# Set-Mile-Bottom.net
KiCad netlist of a schematic drawn in EAGLE
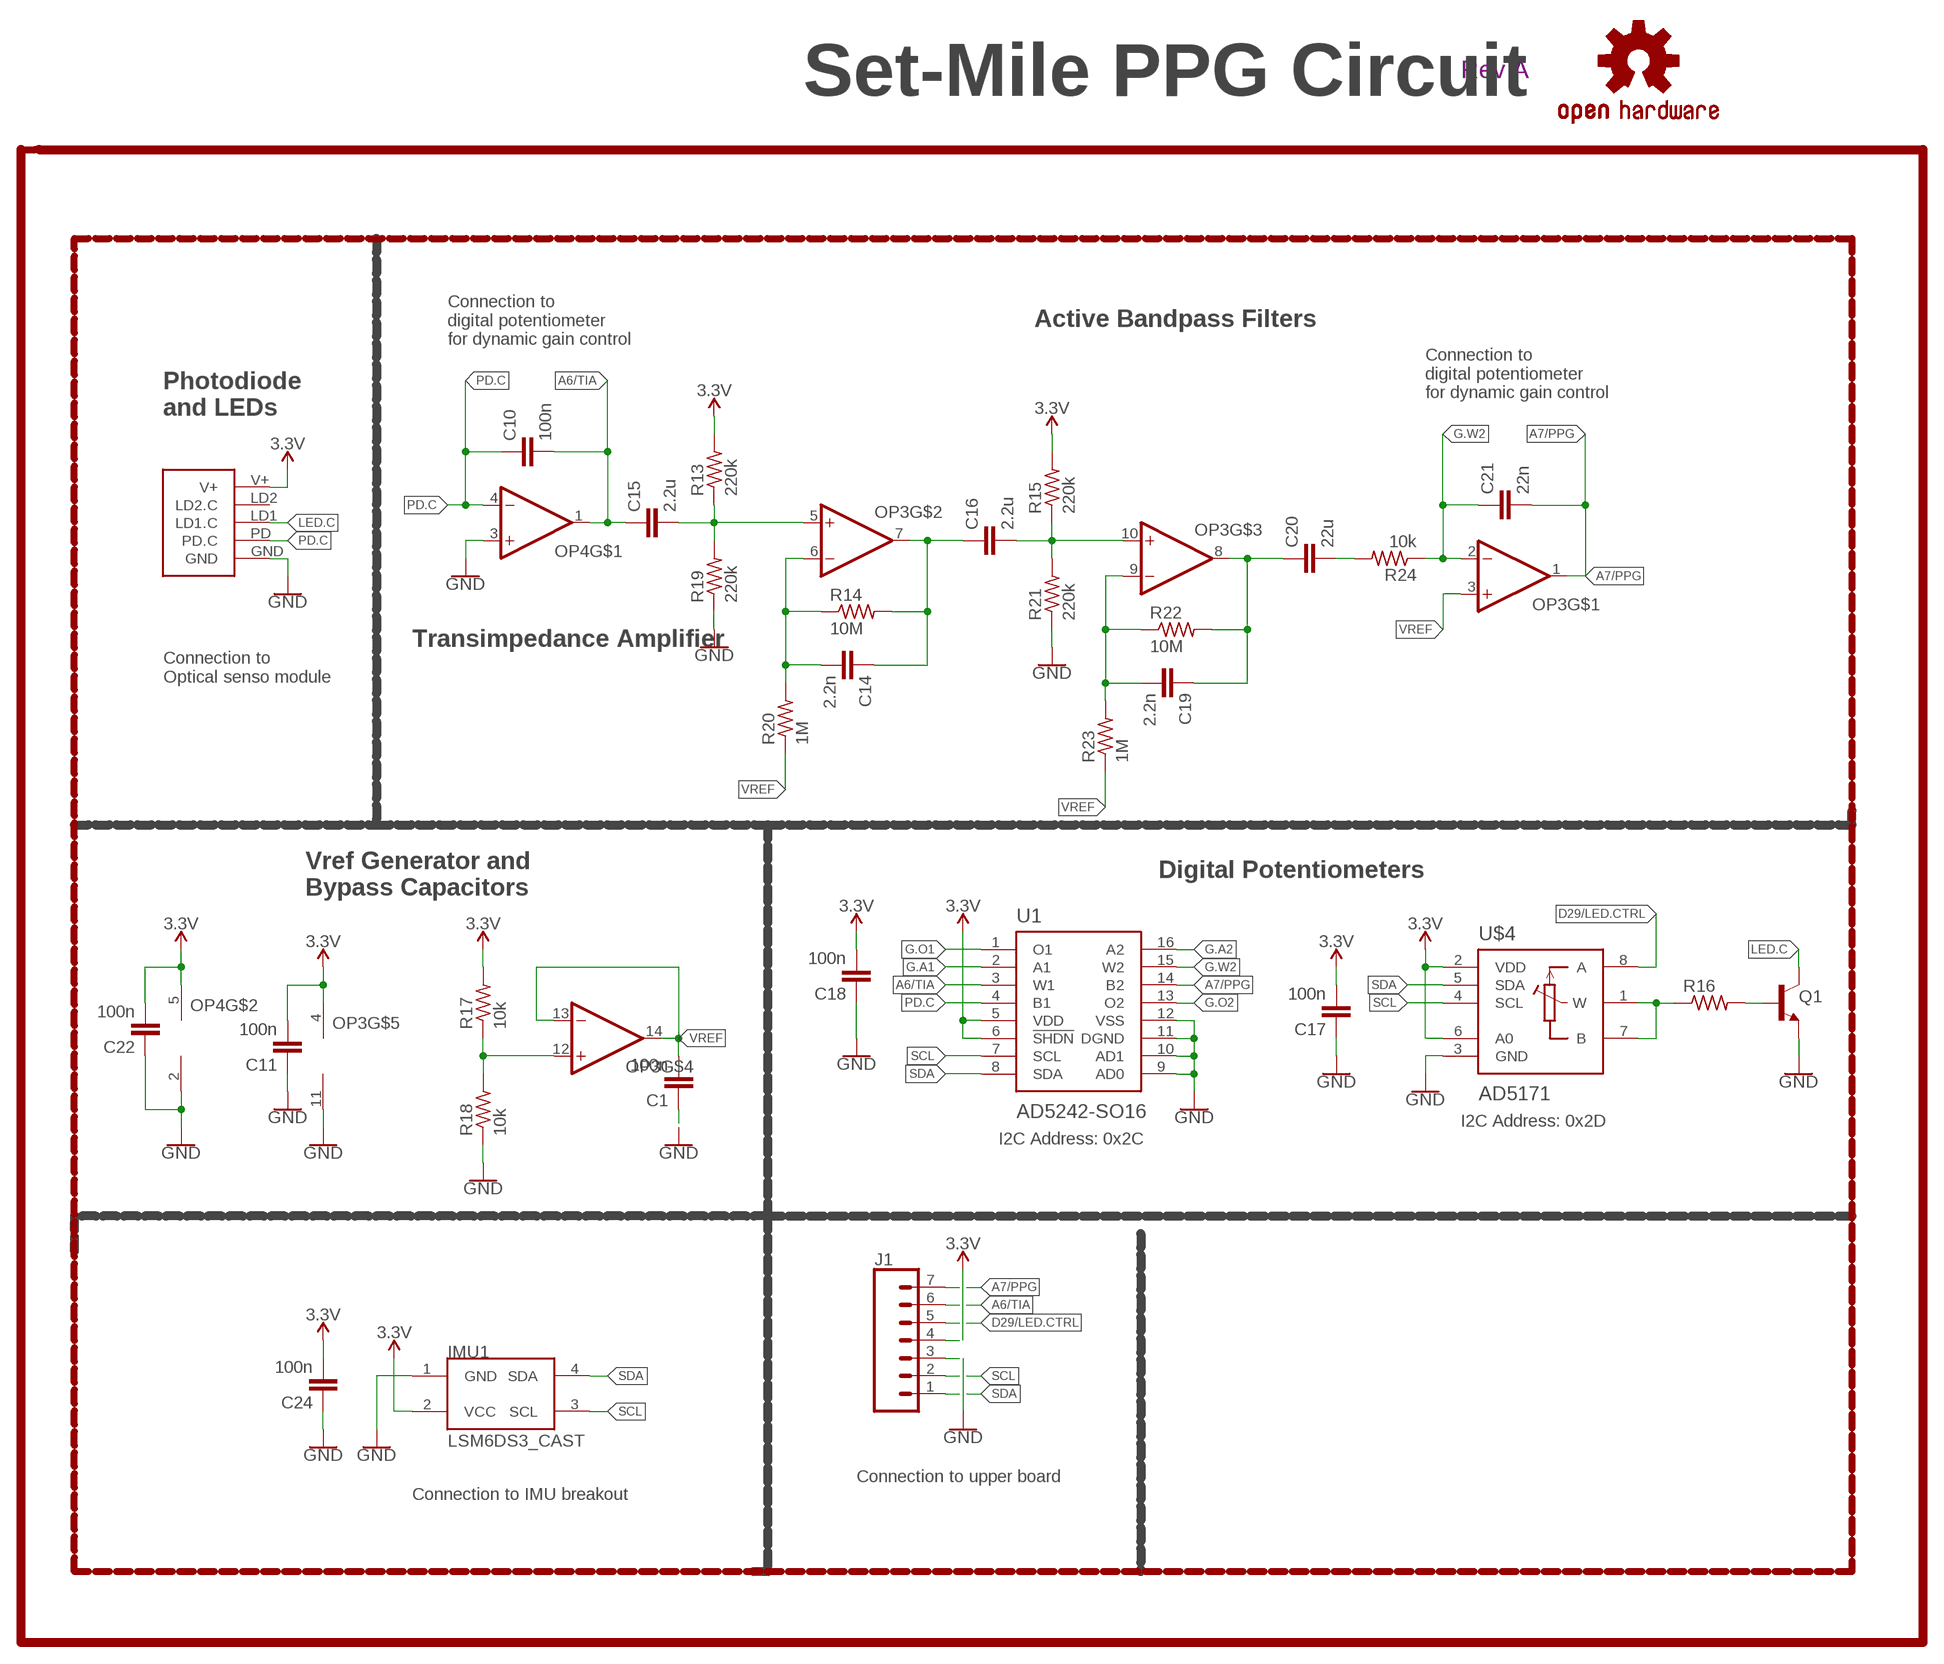
[diagram p0: schematic, sheet 1]

(export (version "E")
  (design (tool "Eeschema 10.0.6"))
  (components
    (comp (ref "C1")
      (value "100n")
      (footprint "eagle-import:C0603")
      (libsource (lib "eagle-import") (part "CAPACITOR0603"))
    )
    (comp (ref "C10")
      (value "100n")
      (footprint "eagle-import:C0603")
      (libsource (lib "eagle-import") (part "CAPACITOR0603"))
    )
    (comp (ref "C11")
      (value "100n")
      (footprint "eagle-import:C0603")
      (libsource (lib "eagle-import") (part "CAPACITOR0603"))
    )
    (comp (ref "C14")
      (value "2.2n")
      (footprint "eagle-import:C0603")
      (libsource (lib "eagle-import") (part "CAPACITOR0603"))
    )
    (comp (ref "C15")
      (value "2.2u")
      (footprint "eagle-import:C0603")
      (libsource (lib "eagle-import") (part "CAPACITOR0603"))
    )
    (comp (ref "C16")
      (value "2.2u")
      (footprint "eagle-import:C0603")
      (libsource (lib "eagle-import") (part "CAPACITOR0603"))
    )
    (comp (ref "C17")
      (value "100n")
      (footprint "eagle-import:C0603")
      (libsource (lib "eagle-import") (part "CAPACITOR0603"))
    )
    (comp (ref "C18")
      (value "100n")
      (footprint "eagle-import:C0603")
      (libsource (lib "eagle-import") (part "CAPACITOR0603"))
    )
    (comp (ref "C19")
      (value "2.2n")
      (footprint "eagle-import:C0603")
      (libsource (lib "eagle-import") (part "CAPACITOR0603"))
    )
    (comp (ref "C20")
      (value "22u")
      (footprint "eagle-import:C0603")
      (libsource (lib "eagle-import") (part "CAPACITOR0603"))
    )
    (comp (ref "C21")
      (value "22n")
      (footprint "eagle-import:C0603")
      (libsource (lib "eagle-import") (part "CAPACITOR0603"))
    )
    (comp (ref "C22")
      (value "100n")
      (footprint "eagle-import:C0603")
      (libsource (lib "eagle-import") (part "CAPACITOR0603"))
    )
    (comp (ref "C24")
      (value "100n")
      (footprint "eagle-import:C0603")
      (libsource (lib "eagle-import") (part "CAPACITOR0603"))
    )
    (comp (ref "IMU1")
      (value "LSM6DS3_CAST")
      (footprint "eagle-import:LSM6DS3_CAST")
      (libsource (lib "eagle-import") (part "LSM6DS3_CAST"))
    )
    (comp (ref "J1")
      (value "CONN_07-1.27MM")
      (footprint "eagle-import:1X07_1.27MM")
      (libsource (lib "eagle-import") (part "CONN_07-1.27MM"))
    )
    (comp (ref "LOGO1")
      (value "REVISION.A")
      (footprint "eagle-import:REV.A")
      (libsource (lib "eagle-import") (part "REVISION.A"))
    )
    (comp (ref "LOGO2")
      (value "OSHW-LOGOL")
      (footprint "eagle-import:OSHW-LOGO-L")
      (libsource (lib "eagle-import") (part "OSHW-LOGOL"))
    )
    (comp (ref "OP3")
      (value "OP-QUAD-SO14")
      (footprint "eagle-import:SO14")
      (libsource (lib "eagle-import") (part "OP-QUAD-SO14"))
    )
    (comp (ref "OP4")
      (value "OP-SINGLEOT")
      (footprint "eagle-import:SOT23-5")
      (libsource (lib "eagle-import") (part "OP-SINGLEOT"))
    )
    (comp (ref "Q1")
      (value "NPN-GENERIC")
      (footprint "eagle-import:SOT23-3")
      (libsource (lib "eagle-import") (part "NPN-GENERIC"))
    )
    (comp (ref "R13")
      (value "220k")
      (footprint "eagle-import:R0603")
      (libsource (lib "eagle-import") (part "RESISTOR0603"))
    )
    (comp (ref "R14")
      (value "10M")
      (footprint "eagle-import:R0603")
      (libsource (lib "eagle-import") (part "RESISTOR0603"))
    )
    (comp (ref "R15")
      (value "220k")
      (footprint "eagle-import:R0603")
      (libsource (lib "eagle-import") (part "RESISTOR0603"))
    )
    (comp (ref "R16")
      (value "RESISTOR0603")
      (footprint "eagle-import:R0603")
      (libsource (lib "eagle-import") (part "RESISTOR0603"))
    )
    (comp (ref "R17")
      (value "10k")
      (footprint "eagle-import:R0402")
      (libsource (lib "eagle-import") (part "RESISTOR0402"))
    )
    (comp (ref "R18")
      (value "10k")
      (footprint "eagle-import:R0402")
      (libsource (lib "eagle-import") (part "RESISTOR0402"))
    )
    (comp (ref "R19")
      (value "220k")
      (footprint "eagle-import:R0603")
      (libsource (lib "eagle-import") (part "RESISTOR0603"))
    )
    (comp (ref "R20")
      (value "1M")
      (footprint "eagle-import:R0603")
      (libsource (lib "eagle-import") (part "RESISTOR0603"))
    )
    (comp (ref "R21")
      (value "220k")
      (footprint "eagle-import:R0603")
      (libsource (lib "eagle-import") (part "RESISTOR0603"))
    )
    (comp (ref "R22")
      (value "10M")
      (footprint "eagle-import:R0603")
      (libsource (lib "eagle-import") (part "RESISTOR0603"))
    )
    (comp (ref "R23")
      (value "1M")
      (footprint "eagle-import:R0603")
      (libsource (lib "eagle-import") (part "RESISTOR0603"))
    )
    (comp (ref "R24")
      (value "10k")
      (footprint "eagle-import:R0603")
      (libsource (lib "eagle-import") (part "RESISTOR0603"))
    )
    (comp (ref "U$3")
      (value "PPG.MODULE.2")
      (footprint "eagle-import:PPG.MODULE.2")
      (libsource (lib "eagle-import") (part "PPG.MODULE.2"))
    )
    (comp (ref "U$4")
      (value "AD5171")
      (footprint "eagle-import:SOT-23-8")
      (libsource (lib "eagle-import") (part "AD5171"))
    )
    (comp (ref "U1")
      (value "AD5242-SO16")
      (footprint "eagle-import:SO16")
      (libsource (lib "eagle-import") (part "AD5242-SO16"))
    )
  )
  (nets
    (net (code "1") (name "3.3V") (class "Default")
      (node (ref "C11") (pin "2") (pinfunction "2_2") (pintype "passive"))
      (node (ref "C17") (pin "2") (pinfunction "2_2") (pintype "passive"))
      (node (ref "C18") (pin "2") (pinfunction "2_2") (pintype "passive"))
      (node (ref "C22") (pin "2") (pinfunction "2_2") (pintype "passive"))
      (node (ref "C24") (pin "2") (pinfunction "2_2") (pintype "passive"))
      (node (ref "IMU1") (pin "2") (pinfunction "VCC_2") (pintype "bidirectional"))
      (node (ref "J1") (pin "4") (pinfunction "4_4") (pintype "passive"))
      (node (ref "OP3") (pin "4") (pinfunction "V+_4") (pintype "power_in"))
      (node (ref "OP4") (pin "5") (pinfunction "V+_5") (pintype "power_in"))
      (node (ref "R13") (pin "2") (pinfunction "2_2") (pintype "passive"))
      (node (ref "R15") (pin "2") (pinfunction "2_2") (pintype "passive"))
      (node (ref "R17") (pin "2") (pinfunction "2_2") (pintype "passive"))
      (node (ref "U$3") (pin "V+") (pinfunction "V+_V+") (pintype "bidirectional"))
      (node (ref "U$4") (pin "2") (pinfunction "VDD_2") (pintype "bidirectional"))
      (node (ref "U$4") (pin "6") (pinfunction "A0_6") (pintype "bidirectional"))
      (node (ref "U1") (pin "5") (pinfunction "VDD_5") (pintype "bidirectional"))
      (node (ref "U1") (pin "6") (pinfunction "~{SHDN}_6") (pintype "bidirectional"))
    )
    (net (code "2") (name "A6{slash}TIA") (class "Default")
      (node (ref "C10") (pin "2") (pinfunction "2_2") (pintype "passive"))
      (node (ref "C15") (pin "1") (pinfunction "1_1") (pintype "passive"))
      (node (ref "J1") (pin "6") (pinfunction "6_6") (pintype "passive"))
      (node (ref "OP4") (pin "1") (pinfunction "OUT_1") (pintype "output"))
      (node (ref "U1") (pin "3") (pinfunction "W1_3") (pintype "bidirectional"))
    )
    (net (code "3") (name "A7{slash}PPG") (class "Default")
      (node (ref "C21") (pin "2") (pinfunction "2_2") (pintype "passive"))
      (node (ref "J1") (pin "7") (pinfunction "7_7") (pintype "passive"))
      (node (ref "OP3") (pin "1") (pinfunction "OUT_1") (pintype "output"))
      (node (ref "U1") (pin "14") (pinfunction "B2_14") (pintype "bidirectional"))
    )
    (net (code "4") (name "D29{slash}LED.CTRL") (class "Default")
      (node (ref "J1") (pin "5") (pinfunction "5_5") (pintype "passive"))
      (node (ref "U$4") (pin "8") (pinfunction "A_8") (pintype "bidirectional"))
    )
    (net (code "5") (name "G.A1") (class "Default")
      (node (ref "U1") (pin "2") (pinfunction "A1_2") (pintype "bidirectional"))
    )
    (net (code "6") (name "G.A2") (class "Default")
      (node (ref "U1") (pin "16") (pinfunction "A2_16") (pintype "bidirectional"))
    )
    (net (code "7") (name "G.O1") (class "Default")
      (node (ref "U1") (pin "1") (pinfunction "O1_1") (pintype "bidirectional"))
    )
    (net (code "8") (name "G.O2") (class "Default")
      (node (ref "U1") (pin "13") (pinfunction "O2_13") (pintype "bidirectional"))
    )
    (net (code "9") (name "G.W2") (class "Default")
      (node (ref "C21") (pin "1") (pinfunction "1_1") (pintype "passive"))
      (node (ref "OP3") (pin "2") (pinfunction "-IN_2") (pintype "input"))
      (node (ref "R24") (pin "1") (pinfunction "1_1") (pintype "passive"))
      (node (ref "U1") (pin "15") (pinfunction "W2_15") (pintype "bidirectional"))
    )
    (net (code "10") (name "GND") (class "Default")
      (node (ref "C1") (pin "1") (pinfunction "1_1") (pintype "passive"))
      (node (ref "C11") (pin "1") (pinfunction "1_1") (pintype "passive"))
      (node (ref "C17") (pin "1") (pinfunction "1_1") (pintype "passive"))
      (node (ref "C18") (pin "1") (pinfunction "1_1") (pintype "passive"))
      (node (ref "C22") (pin "1") (pinfunction "1_1") (pintype "passive"))
      (node (ref "C24") (pin "1") (pinfunction "1_1") (pintype "passive"))
      (node (ref "IMU1") (pin "1") (pinfunction "GND_1") (pintype "bidirectional"))
      (node (ref "J1") (pin "3") (pinfunction "3_3") (pintype "passive"))
      (node (ref "OP3") (pin "11") (pinfunction "V-_11") (pintype "power_in"))
      (node (ref "OP4") (pin "2") (pinfunction "V-_2") (pintype "power_in"))
      (node (ref "OP4") (pin "3") (pinfunction "+IN_3") (pintype "input"))
      (node (ref "Q1") (pin "2") (pinfunction "E_2") (pintype "passive"))
      (node (ref "R18") (pin "1") (pinfunction "1_1") (pintype "passive"))
      (node (ref "R19") (pin "1") (pinfunction "1_1") (pintype "passive"))
      (node (ref "R21") (pin "1") (pinfunction "1_1") (pintype "passive"))
      (node (ref "U$3") (pin "GND") (pinfunction "GND_GND") (pintype "bidirectional"))
      (node (ref "U$4") (pin "3") (pinfunction "GND_3") (pintype "bidirectional"))
      (node (ref "U1") (pin "10") (pinfunction "AD1_10") (pintype "bidirectional"))
      (node (ref "U1") (pin "11") (pinfunction "DGND_11") (pintype "bidirectional"))
      (node (ref "U1") (pin "12") (pinfunction "VSS_12") (pintype "bidirectional"))
      (node (ref "U1") (pin "9") (pinfunction "AD0_9") (pintype "bidirectional"))
    )
    (net (code "11") (name "LED.C") (class "Default")
      (node (ref "Q1") (pin "3") (pinfunction "C_3") (pintype "passive"))
      (node (ref "U$3") (pin "LD1") (pinfunction "LD1.C_LD1") (pintype "bidirectional"))
    )
    (net (code "12") (name "Net-(C20-Pad2)") (class "Default")
      (node (ref "C20") (pin "2") (pinfunction "2_2") (pintype "passive"))
      (node (ref "R24") (pin "2") (pinfunction "2_2") (pintype "passive"))
    )
    (net (code "13") (name "Net-(OP3B-+IN)") (class "Default")
      (node (ref "C15") (pin "2") (pinfunction "2_2") (pintype "passive"))
      (node (ref "OP3") (pin "5") (pinfunction "+IN_5") (pintype "input"))
      (node (ref "R13") (pin "1") (pinfunction "1_1") (pintype "passive"))
      (node (ref "R19") (pin "2") (pinfunction "2_2") (pintype "passive"))
    )
    (net (code "14") (name "Net-(OP3B--IN)") (class "Default")
      (node (ref "C14") (pin "2") (pinfunction "2_2") (pintype "passive"))
      (node (ref "OP3") (pin "6") (pinfunction "-IN_6") (pintype "input"))
      (node (ref "R14") (pin "1") (pinfunction "1_1") (pintype "passive"))
      (node (ref "R20") (pin "2") (pinfunction "2_2") (pintype "passive"))
    )
    (net (code "15") (name "Net-(OP3B-OUT)") (class "Default")
      (node (ref "C14") (pin "1") (pinfunction "1_1") (pintype "passive"))
      (node (ref "C16") (pin "1") (pinfunction "1_1") (pintype "passive"))
      (node (ref "OP3") (pin "7") (pinfunction "OUT_7") (pintype "output"))
      (node (ref "R14") (pin "2") (pinfunction "2_2") (pintype "passive"))
    )
    (net (code "16") (name "Net-(OP3C-+IN)") (class "Default")
      (node (ref "C16") (pin "2") (pinfunction "2_2") (pintype "passive"))
      (node (ref "OP3") (pin "10") (pinfunction "+IN_10") (pintype "input"))
      (node (ref "R15") (pin "1") (pinfunction "1_1") (pintype "passive"))
      (node (ref "R21") (pin "2") (pinfunction "2_2") (pintype "passive"))
    )
    (net (code "17") (name "Net-(OP3C--IN)") (class "Default")
      (node (ref "C19") (pin "2") (pinfunction "2_2") (pintype "passive"))
      (node (ref "OP3") (pin "9") (pinfunction "-IN_9") (pintype "input"))
      (node (ref "R22") (pin "1") (pinfunction "1_1") (pintype "passive"))
      (node (ref "R23") (pin "2") (pinfunction "2_2") (pintype "passive"))
    )
    (net (code "18") (name "Net-(OP3C-OUT)") (class "Default")
      (node (ref "C19") (pin "1") (pinfunction "1_1") (pintype "passive"))
      (node (ref "C20") (pin "1") (pinfunction "1_1") (pintype "passive"))
      (node (ref "OP3") (pin "8") (pinfunction "OUT_8") (pintype "output"))
      (node (ref "R22") (pin "2") (pinfunction "2_2") (pintype "passive"))
    )
    (net (code "19") (name "Net-(OP3D-+IN)") (class "Default")
      (node (ref "OP3") (pin "12") (pinfunction "+IN_12") (pintype "input"))
      (node (ref "R17") (pin "1") (pinfunction "1_1") (pintype "passive"))
      (node (ref "R18") (pin "2") (pinfunction "2_2") (pintype "passive"))
    )
    (net (code "20") (name "Net-(Q1-B)") (class "Default")
      (node (ref "Q1") (pin "1") (pinfunction "B_1") (pintype "passive"))
      (node (ref "R16") (pin "2") (pinfunction "2_2") (pintype "passive"))
    )
    (net (code "21") (name "Net-(U$4-B)") (class "Default")
      (node (ref "R16") (pin "1") (pinfunction "1_1") (pintype "passive"))
      (node (ref "U$4") (pin "1") (pinfunction "W_1") (pintype "bidirectional"))
      (node (ref "U$4") (pin "7") (pinfunction "B_7") (pintype "bidirectional"))
    )
    (net (code "22") (name "PD.C") (class "Default")
      (node (ref "C10") (pin "1") (pinfunction "1_1") (pintype "passive"))
      (node (ref "OP4") (pin "4") (pinfunction "-IN_4") (pintype "input"))
      (node (ref "U$3") (pin "PD") (pinfunction "PD.C_PD") (pintype "bidirectional"))
      (node (ref "U1") (pin "4") (pinfunction "B1_4") (pintype "bidirectional"))
    )
    (net (code "23") (name "SCL") (class "Default")
      (node (ref "IMU1") (pin "3") (pinfunction "SCL_3") (pintype "bidirectional"))
      (node (ref "J1") (pin "2") (pinfunction "2_2") (pintype "passive"))
      (node (ref "U$4") (pin "4") (pinfunction "SCL_4") (pintype "bidirectional"))
      (node (ref "U1") (pin "7") (pinfunction "SCL_7") (pintype "bidirectional"))
    )
    (net (code "24") (name "SDA") (class "Default")
      (node (ref "IMU1") (pin "4") (pinfunction "SDA_4") (pintype "bidirectional"))
      (node (ref "J1") (pin "1") (pinfunction "1_1") (pintype "passive"))
      (node (ref "U$4") (pin "5") (pinfunction "SDA_5") (pintype "bidirectional"))
      (node (ref "U1") (pin "8") (pinfunction "SDA_8") (pintype "bidirectional"))
    )
    (net (code "25") (name "VREF") (class "Default")
      (node (ref "C1") (pin "2") (pinfunction "2_2") (pintype "passive"))
      (node (ref "OP3") (pin "13") (pinfunction "-IN_13") (pintype "input"))
      (node (ref "OP3") (pin "14") (pinfunction "OUT_14") (pintype "output"))
      (node (ref "OP3") (pin "3") (pinfunction "+IN_3") (pintype "input"))
      (node (ref "R20") (pin "1") (pinfunction "1_1") (pintype "passive"))
      (node (ref "R23") (pin "1") (pinfunction "1_1") (pintype "passive"))
    )
    (net (code "26") (name "unconnected-(U$3-LD2.C-PadLD2)") (class "Default")
      (node (ref "U$3") (pin "LD2") (pinfunction "LD2.C_LD2") (pintype "bidirectional"))
    )
  )
)
